# Power.net
KiCad netlist of a schematic drawn in Altium Designer
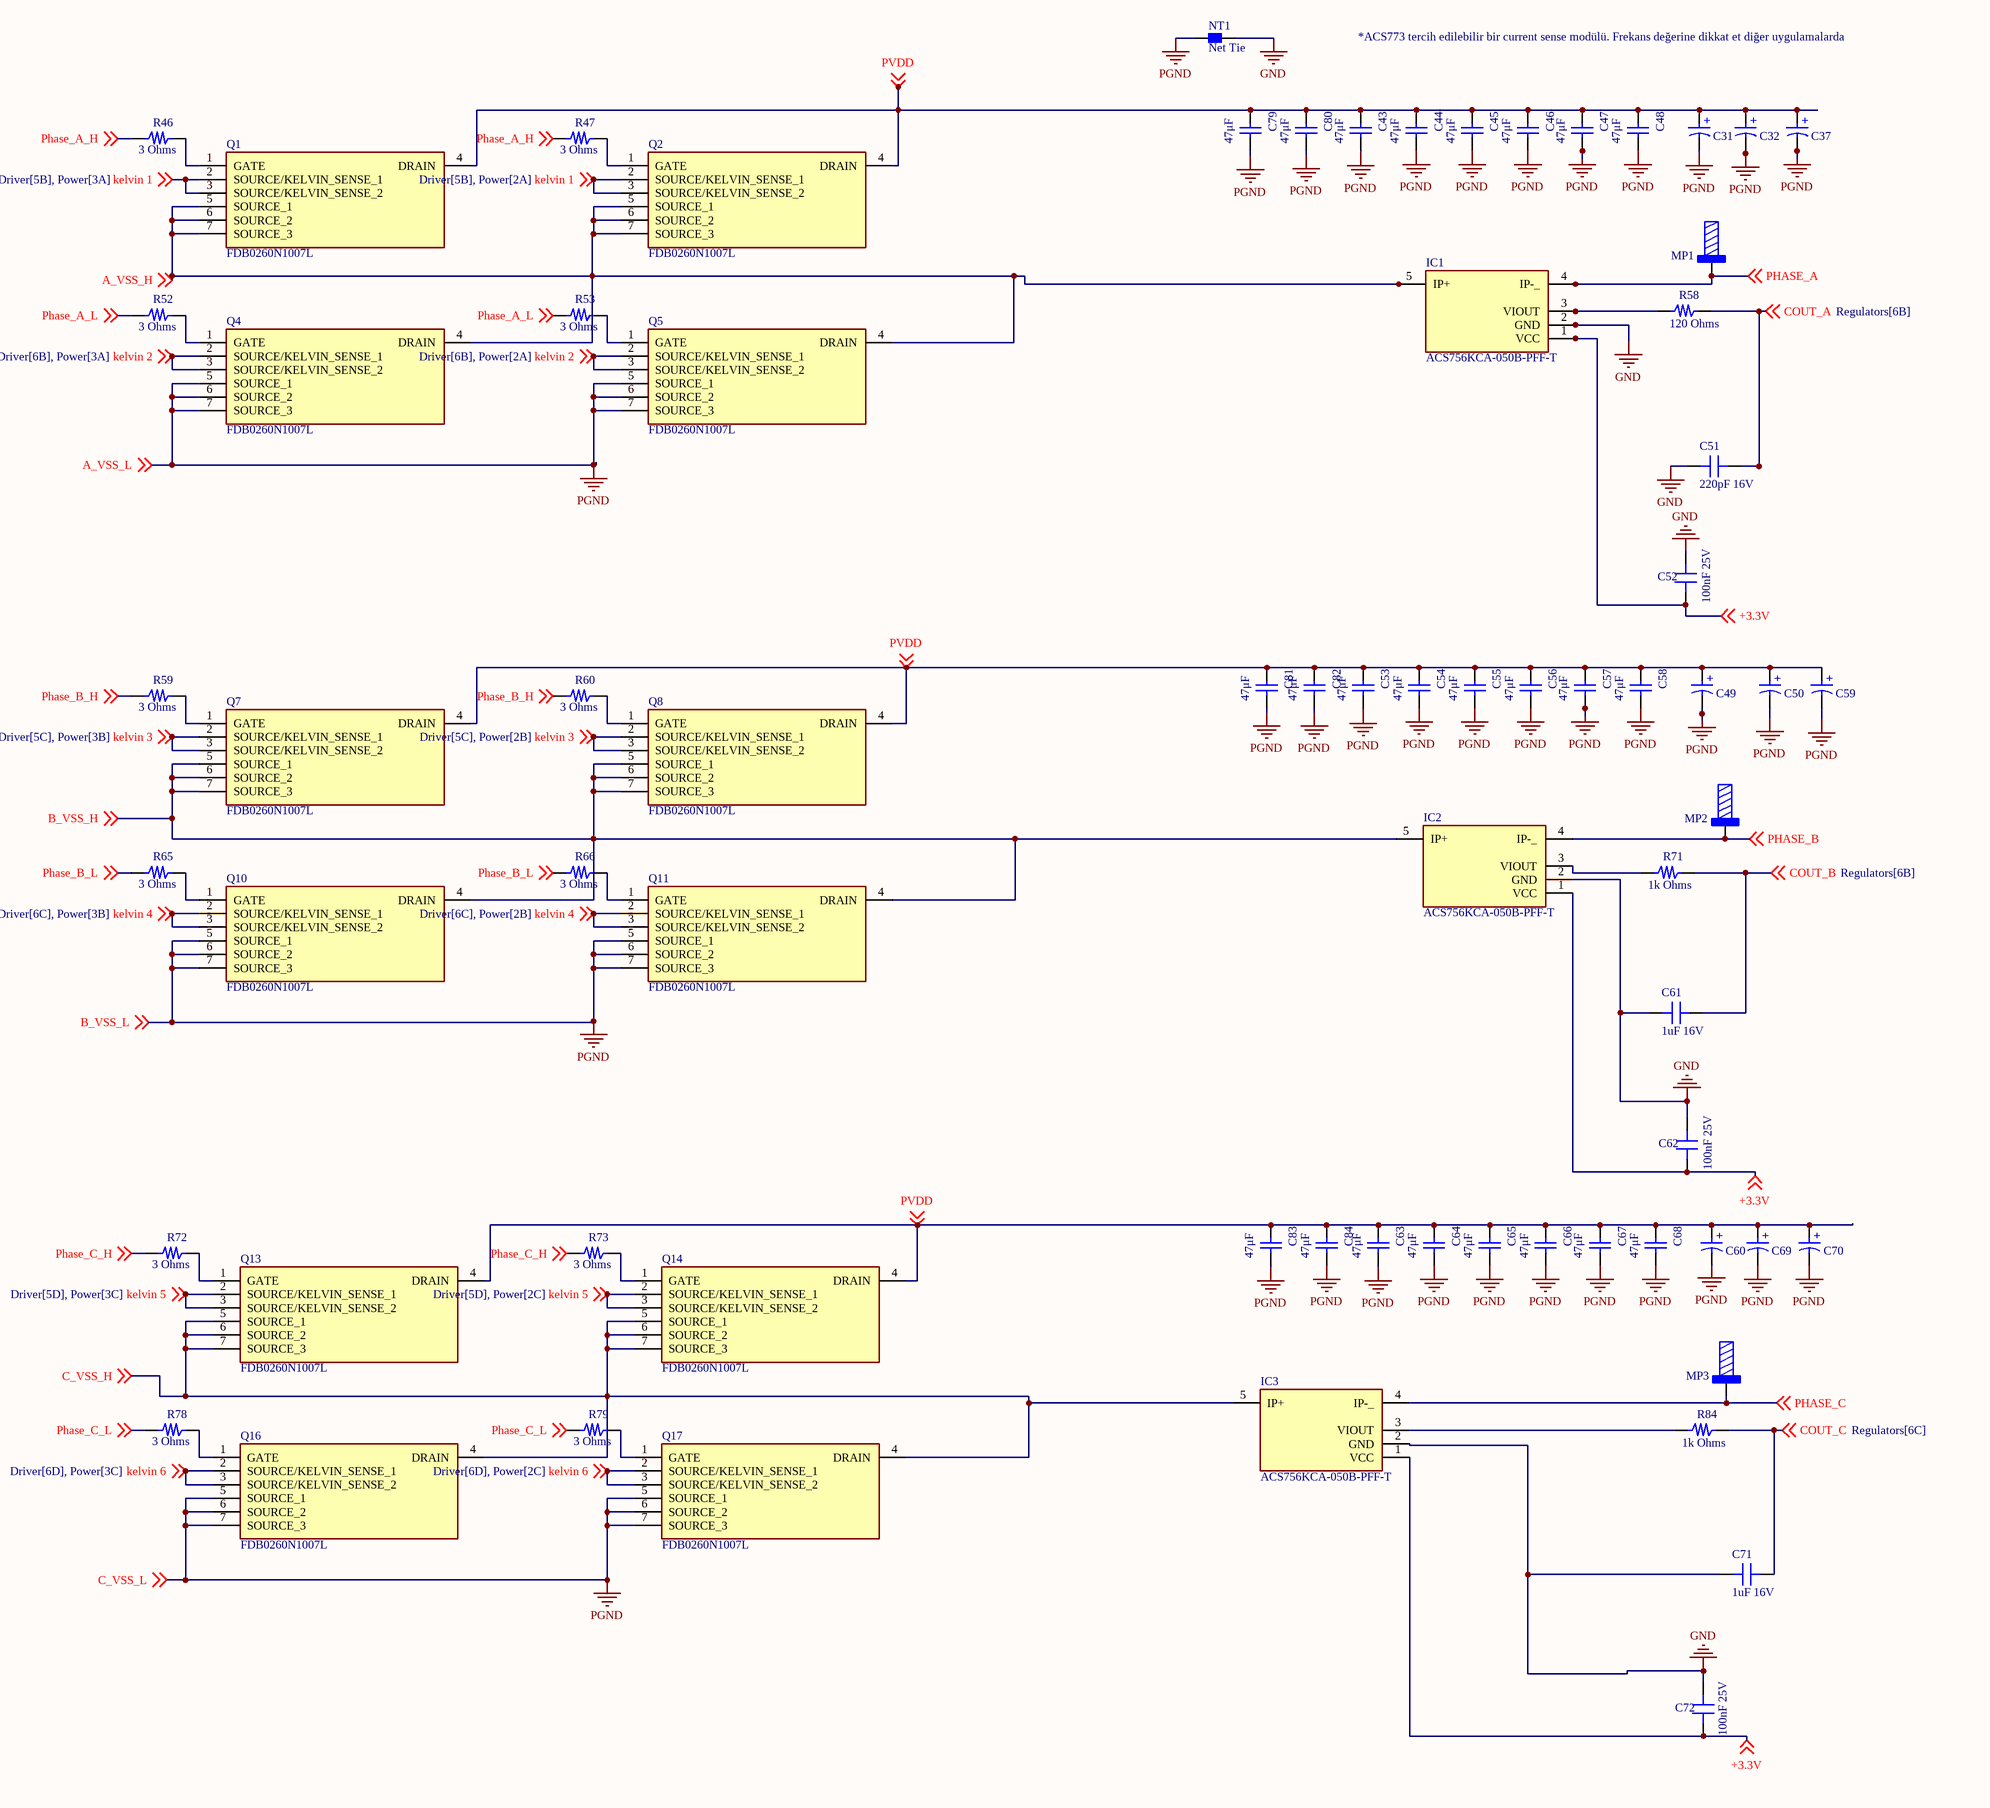
[diagram p0: Power.SchDoc]

(export (version "E")
  (design (tool "Eeschema 10.0.6"))
  (components
    (comp (ref "C31")
      (value "470µF")
      (footprint "WCAP-ATUL_D18H31.5")
      (description "WCAP-ATUL Aluminum Electrolytic Capacitor, Radial, THT, D18 x H31.5mm, 470µF, 100V")
      (fields
        (field (name "MANUFACTURER PART NUMBER") "860040881012")
        (field (name "MANUFACTURER") "Wurth Elektronik")
      )
      (libsource (lib "Altium_WCAP-ATUL (rev22e) (1)") (part "860040881012"))
    )
    (comp (ref "C32")
      (value "470µF")
      (footprint "WCAP-ATUL_D18H31.5")
      (description "WCAP-ATUL Aluminum Electrolytic Capacitor, Radial, THT, D18 x H31.5mm, 470µF, 100V")
      (fields
        (field (name "MANUFACTURER PART NUMBER") "860040881012")
        (field (name "MANUFACTURER") "Wurth Elektronik")
      )
      (libsource (lib "Altium_WCAP-ATUL (rev22e) (1)") (part "860040881012"))
    )
    (comp (ref "C37")
      (value "470µF")
      (footprint "WCAP-ATUL_D18H31.5")
      (description "WCAP-ATUL Aluminum Electrolytic Capacitor, Radial, THT, D18 x H31.5mm, 470µF, 100V")
      (fields
        (field (name "MANUFACTURER PART NUMBER") "860040881012")
        (field (name "MANUFACTURER") "Wurth Elektronik")
      )
      (libsource (lib "Altium_WCAP-ATUL (rev22e) (1)") (part "860040881012"))
    )
    (comp (ref "C43")
      (value "47μF")
      (footprint "WCAP-CSGP_1210_L3.2W2.5H2.5")
      (description "WCAP-CSGP Multilayer Ceramic Chip Capacitor, General Purpose, size 1210, X5R, 47μF, 10V")
      (fields
        (field (name "MANUFACTURER PART NUMBER") "885012109007")
        (field (name "MANUFACTURER") "Wurth Elektronik")
      )
      (libsource (lib "Altium_WCAP-CSGP (rev24c)") (part "885012109007"))
    )
    (comp (ref "C44")
      (value "47μF")
      (footprint "WCAP-CSGP_1210_L3.2W2.5H2.5")
      (description "WCAP-CSGP Multilayer Ceramic Chip Capacitor, General Purpose, size 1210, X5R, 47μF, 10V")
      (fields
        (field (name "MANUFACTURER PART NUMBER") "885012109007")
        (field (name "MANUFACTURER") "Wurth Elektronik")
      )
      (libsource (lib "Altium_WCAP-CSGP (rev24c)") (part "885012109007"))
    )
    (comp (ref "C45")
      (value "47μF")
      (footprint "WCAP-CSGP_1210_L3.2W2.5H2.5")
      (description "WCAP-CSGP Multilayer Ceramic Chip Capacitor, General Purpose, size 1210, X5R, 47μF, 10V")
      (fields
        (field (name "MANUFACTURER PART NUMBER") "885012109007")
        (field (name "MANUFACTURER") "Wurth Elektronik")
      )
      (libsource (lib "Altium_WCAP-CSGP (rev24c)") (part "885012109007"))
    )
    (comp (ref "C46")
      (value "47μF")
      (footprint "WCAP-CSGP_1210_L3.2W2.5H2.5")
      (description "WCAP-CSGP Multilayer Ceramic Chip Capacitor, General Purpose, size 1210, X5R, 47μF, 10V")
      (fields
        (field (name "MANUFACTURER PART NUMBER") "885012109007")
        (field (name "MANUFACTURER") "Wurth Elektronik")
      )
      (libsource (lib "Altium_WCAP-CSGP (rev24c)") (part "885012109007"))
    )
    (comp (ref "C47")
      (value "47μF")
      (footprint "WCAP-CSGP_1210_L3.2W2.5H2.5")
      (description "WCAP-CSGP Multilayer Ceramic Chip Capacitor, General Purpose, size 1210, X5R, 47μF, 10V")
      (fields
        (field (name "MANUFACTURER PART NUMBER") "885012109007")
        (field (name "MANUFACTURER") "Wurth Elektronik")
      )
      (libsource (lib "Altium_WCAP-CSGP (rev24c)") (part "885012109007"))
    )
    (comp (ref "C48")
      (value "47μF")
      (footprint "WCAP-CSGP_1210_L3.2W2.5H2.5")
      (description "WCAP-CSGP Multilayer Ceramic Chip Capacitor, General Purpose, size 1210, X5R, 47μF, 10V")
      (fields
        (field (name "MANUFACTURER PART NUMBER") "885012109007")
        (field (name "MANUFACTURER") "Wurth Elektronik")
      )
      (libsource (lib "Altium_WCAP-CSGP (rev24c)") (part "885012109007"))
    )
    (comp (ref "C49")
      (value "470µF")
      (footprint "WCAP-ATUL_D18H31.5")
      (description "WCAP-ATUL Aluminum Electrolytic Capacitor, Radial, THT, D18 x H31.5mm, 470µF, 100V")
      (fields
        (field (name "MANUFACTURER PART NUMBER") "860040881012")
        (field (name "MANUFACTURER") "Wurth Elektronik")
      )
      (libsource (lib "Altium_WCAP-ATUL (rev22e) (1)") (part "860040881012"))
    )
    (comp (ref "C50")
      (value "470µF")
      (footprint "WCAP-ATUL_D18H31.5")
      (description "WCAP-ATUL Aluminum Electrolytic Capacitor, Radial, THT, D18 x H31.5mm, 470µF, 100V")
      (fields
        (field (name "MANUFACTURER PART NUMBER") "860040881012")
        (field (name "MANUFACTURER") "Wurth Elektronik")
      )
      (libsource (lib "Altium_WCAP-ATUL (rev22e) (1)") (part "860040881012"))
    )
    (comp (ref "C51")
      (value "220pF 16V")
      (footprint "0603_CAP")
      (description "CL10B105KO8NNNC - MLCC (1608) 0603 1uF 16VDC ±10% X7R")
      (libsource (lib "HidroanaSCHLib") (part "CAP_0603"))
    )
    (comp (ref "C52")
      (value "100nF 25V")
      (footprint "0603_CAP")
      (description "CL10B105KO8NNNC - MLCC (1608) 0603 1uF 16VDC ±10% X7R")
      (libsource (lib "HidroanaSCHLib") (part "CAP_0603"))
    )
    (comp (ref "C53")
      (value "47μF")
      (footprint "WCAP-CSGP_1210_L3.2W2.5H2.5")
      (description "WCAP-CSGP Multilayer Ceramic Chip Capacitor, General Purpose, size 1210, X5R, 47μF, 10V")
      (fields
        (field (name "MANUFACTURER PART NUMBER") "885012109007")
        (field (name "MANUFACTURER") "Wurth Elektronik")
      )
      (libsource (lib "Altium_WCAP-CSGP (rev24c)") (part "885012109007"))
    )
    (comp (ref "C54")
      (value "47μF")
      (footprint "WCAP-CSGP_1210_L3.2W2.5H2.5")
      (description "WCAP-CSGP Multilayer Ceramic Chip Capacitor, General Purpose, size 1210, X5R, 47μF, 10V")
      (fields
        (field (name "MANUFACTURER PART NUMBER") "885012109007")
        (field (name "MANUFACTURER") "Wurth Elektronik")
      )
      (libsource (lib "Altium_WCAP-CSGP (rev24c)") (part "885012109007"))
    )
    (comp (ref "C55")
      (value "47μF")
      (footprint "WCAP-CSGP_1210_L3.2W2.5H2.5")
      (description "WCAP-CSGP Multilayer Ceramic Chip Capacitor, General Purpose, size 1210, X5R, 47μF, 10V")
      (fields
        (field (name "MANUFACTURER PART NUMBER") "885012109007")
        (field (name "MANUFACTURER") "Wurth Elektronik")
      )
      (libsource (lib "Altium_WCAP-CSGP (rev24c)") (part "885012109007"))
    )
    (comp (ref "C56")
      (value "47μF")
      (footprint "WCAP-CSGP_1210_L3.2W2.5H2.5")
      (description "WCAP-CSGP Multilayer Ceramic Chip Capacitor, General Purpose, size 1210, X5R, 47μF, 10V")
      (fields
        (field (name "MANUFACTURER PART NUMBER") "885012109007")
        (field (name "MANUFACTURER") "Wurth Elektronik")
      )
      (libsource (lib "Altium_WCAP-CSGP (rev24c)") (part "885012109007"))
    )
    (comp (ref "C57")
      (value "47μF")
      (footprint "WCAP-CSGP_1210_L3.2W2.5H2.5")
      (description "WCAP-CSGP Multilayer Ceramic Chip Capacitor, General Purpose, size 1210, X5R, 47μF, 10V")
      (fields
        (field (name "MANUFACTURER PART NUMBER") "885012109007")
        (field (name "MANUFACTURER") "Wurth Elektronik")
      )
      (libsource (lib "Altium_WCAP-CSGP (rev24c)") (part "885012109007"))
    )
    (comp (ref "C58")
      (value "47μF")
      (footprint "WCAP-CSGP_1210_L3.2W2.5H2.5")
      (description "WCAP-CSGP Multilayer Ceramic Chip Capacitor, General Purpose, size 1210, X5R, 47μF, 10V")
      (fields
        (field (name "MANUFACTURER PART NUMBER") "885012109007")
        (field (name "MANUFACTURER") "Wurth Elektronik")
      )
      (libsource (lib "Altium_WCAP-CSGP (rev24c)") (part "885012109007"))
    )
    (comp (ref "C59")
      (value "470µF")
      (footprint "WCAP-ATUL_D18H31.5")
      (description "WCAP-ATUL Aluminum Electrolytic Capacitor, Radial, THT, D18 x H31.5mm, 470µF, 100V")
      (fields
        (field (name "MANUFACTURER PART NUMBER") "860040881012")
        (field (name "MANUFACTURER") "Wurth Elektronik")
      )
      (libsource (lib "Altium_WCAP-ATUL (rev22e) (1)") (part "860040881012"))
    )
    (comp (ref "C60")
      (value "470µF")
      (footprint "WCAP-ATUL_D18H31.5")
      (description "WCAP-ATUL Aluminum Electrolytic Capacitor, Radial, THT, D18 x H31.5mm, 470µF, 100V")
      (fields
        (field (name "MANUFACTURER PART NUMBER") "860040881012")
        (field (name "MANUFACTURER") "Wurth Elektronik")
      )
      (libsource (lib "Altium_WCAP-ATUL (rev22e) (1)") (part "860040881012"))
    )
    (comp (ref "C61")
      (value "1uF 16V")
      (footprint "0603_CAP")
      (description "CL10B105KO8NNNC - MLCC (1608) 0603 1uF 16VDC ±10% X7R")
      (libsource (lib "HidroanaSCHLib") (part "CAP_0603"))
    )
    (comp (ref "C62")
      (value "100nF 25V")
      (footprint "0603_CAP")
      (description "CL10B105KO8NNNC - MLCC (1608) 0603 1uF 16VDC ±10% X7R")
      (libsource (lib "HidroanaSCHLib") (part "CAP_0603"))
    )
    (comp (ref "C63")
      (value "47μF")
      (footprint "WCAP-CSGP_1210_L3.2W2.5H2.5")
      (description "WCAP-CSGP Multilayer Ceramic Chip Capacitor, General Purpose, size 1210, X5R, 47μF, 10V")
      (fields
        (field (name "MANUFACTURER PART NUMBER") "885012109007")
        (field (name "MANUFACTURER") "Wurth Elektronik")
      )
      (libsource (lib "Altium_WCAP-CSGP (rev24c)") (part "885012109007"))
    )
    (comp (ref "C64")
      (value "47μF")
      (footprint "WCAP-CSGP_1210_L3.2W2.5H2.5")
      (description "WCAP-CSGP Multilayer Ceramic Chip Capacitor, General Purpose, size 1210, X5R, 47μF, 10V")
      (fields
        (field (name "MANUFACTURER PART NUMBER") "885012109007")
        (field (name "MANUFACTURER") "Wurth Elektronik")
      )
      (libsource (lib "Altium_WCAP-CSGP (rev24c)") (part "885012109007"))
    )
    (comp (ref "C65")
      (value "47μF")
      (footprint "WCAP-CSGP_1210_L3.2W2.5H2.5")
      (description "WCAP-CSGP Multilayer Ceramic Chip Capacitor, General Purpose, size 1210, X5R, 47μF, 10V")
      (fields
        (field (name "MANUFACTURER PART NUMBER") "885012109007")
        (field (name "MANUFACTURER") "Wurth Elektronik")
      )
      (libsource (lib "Altium_WCAP-CSGP (rev24c)") (part "885012109007"))
    )
    (comp (ref "C66")
      (value "47μF")
      (footprint "WCAP-CSGP_1210_L3.2W2.5H2.5")
      (description "WCAP-CSGP Multilayer Ceramic Chip Capacitor, General Purpose, size 1210, X5R, 47μF, 10V")
      (fields
        (field (name "MANUFACTURER PART NUMBER") "885012109007")
        (field (name "MANUFACTURER") "Wurth Elektronik")
      )
      (libsource (lib "Altium_WCAP-CSGP (rev24c)") (part "885012109007"))
    )
    (comp (ref "C67")
      (value "47μF")
      (footprint "WCAP-CSGP_1210_L3.2W2.5H2.5")
      (description "WCAP-CSGP Multilayer Ceramic Chip Capacitor, General Purpose, size 1210, X5R, 47μF, 10V")
      (fields
        (field (name "MANUFACTURER PART NUMBER") "885012109007")
        (field (name "MANUFACTURER") "Wurth Elektronik")
      )
      (libsource (lib "Altium_WCAP-CSGP (rev24c)") (part "885012109007"))
    )
    (comp (ref "C68")
      (value "47μF")
      (footprint "WCAP-CSGP_1210_L3.2W2.5H2.5")
      (description "WCAP-CSGP Multilayer Ceramic Chip Capacitor, General Purpose, size 1210, X5R, 47μF, 10V")
      (fields
        (field (name "MANUFACTURER PART NUMBER") "885012109007")
        (field (name "MANUFACTURER") "Wurth Elektronik")
      )
      (libsource (lib "Altium_WCAP-CSGP (rev24c)") (part "885012109007"))
    )
    (comp (ref "C69")
      (value "470µF")
      (footprint "WCAP-ATUL_D18H31.5")
      (description "WCAP-ATUL Aluminum Electrolytic Capacitor, Radial, THT, D18 x H31.5mm, 470µF, 100V")
      (fields
        (field (name "MANUFACTURER PART NUMBER") "860040881012")
        (field (name "MANUFACTURER") "Wurth Elektronik")
      )
      (libsource (lib "Altium_WCAP-ATUL (rev22e) (1)") (part "860040881012"))
    )
    (comp (ref "C70")
      (value "470µF")
      (footprint "WCAP-ATUL_D18H31.5")
      (description "WCAP-ATUL Aluminum Electrolytic Capacitor, Radial, THT, D18 x H31.5mm, 470µF, 100V")
      (fields
        (field (name "MANUFACTURER PART NUMBER") "860040881012")
        (field (name "MANUFACTURER") "Wurth Elektronik")
      )
      (libsource (lib "Altium_WCAP-ATUL (rev22e) (1)") (part "860040881012"))
    )
    (comp (ref "C71")
      (value "1uF 16V")
      (footprint "0603_CAP")
      (description "CL10B105KO8NNNC - MLCC (1608) 0603 1uF 16VDC ±10% X7R")
      (libsource (lib "HidroanaSCHLib") (part "CAP_0603"))
    )
    (comp (ref "C72")
      (value "100nF 25V")
      (footprint "0603_CAP")
      (description "CL10B105KO8NNNC - MLCC (1608) 0603 1uF 16VDC ±10% X7R")
      (libsource (lib "HidroanaSCHLib") (part "CAP_0603"))
    )
    (comp (ref "C79")
      (value "47μF")
      (footprint "WCAP-CSGP_1210_L3.2W2.5H2.5")
      (description "WCAP-CSGP Multilayer Ceramic Chip Capacitor, General Purpose, size 1210, X5R, 47μF, 10V")
      (fields
        (field (name "MANUFACTURER PART NUMBER") "885012109007")
        (field (name "MANUFACTURER") "Wurth Elektronik")
      )
      (libsource (lib "Altium_WCAP-CSGP (rev24c)") (part "885012109007"))
    )
    (comp (ref "C80")
      (value "47μF")
      (footprint "WCAP-CSGP_1210_L3.2W2.5H2.5")
      (description "WCAP-CSGP Multilayer Ceramic Chip Capacitor, General Purpose, size 1210, X5R, 47μF, 10V")
      (fields
        (field (name "MANUFACTURER PART NUMBER") "885012109007")
        (field (name "MANUFACTURER") "Wurth Elektronik")
      )
      (libsource (lib "Altium_WCAP-CSGP (rev24c)") (part "885012109007"))
    )
    (comp (ref "C81")
      (value "47μF")
      (footprint "WCAP-CSGP_1210_L3.2W2.5H2.5")
      (description "WCAP-CSGP Multilayer Ceramic Chip Capacitor, General Purpose, size 1210, X5R, 47μF, 10V")
      (fields
        (field (name "MANUFACTURER PART NUMBER") "885012109007")
        (field (name "MANUFACTURER") "Wurth Elektronik")
      )
      (libsource (lib "Altium_WCAP-CSGP (rev24c)") (part "885012109007"))
    )
    (comp (ref "C82")
      (value "47μF")
      (footprint "WCAP-CSGP_1210_L3.2W2.5H2.5")
      (description "WCAP-CSGP Multilayer Ceramic Chip Capacitor, General Purpose, size 1210, X5R, 47μF, 10V")
      (fields
        (field (name "MANUFACTURER PART NUMBER") "885012109007")
        (field (name "MANUFACTURER") "Wurth Elektronik")
      )
      (libsource (lib "Altium_WCAP-CSGP (rev24c)") (part "885012109007"))
    )
    (comp (ref "C83")
      (value "47μF")
      (footprint "WCAP-CSGP_1210_L3.2W2.5H2.5")
      (description "WCAP-CSGP Multilayer Ceramic Chip Capacitor, General Purpose, size 1210, X5R, 47μF, 10V")
      (fields
        (field (name "MANUFACTURER PART NUMBER") "885012109007")
        (field (name "MANUFACTURER") "Wurth Elektronik")
      )
      (libsource (lib "Altium_WCAP-CSGP (rev24c)") (part "885012109007"))
    )
    (comp (ref "C84")
      (value "47μF")
      (footprint "WCAP-CSGP_1210_L3.2W2.5H2.5")
      (description "WCAP-CSGP Multilayer Ceramic Chip Capacitor, General Purpose, size 1210, X5R, 47μF, 10V")
      (fields
        (field (name "MANUFACTURER PART NUMBER") "885012109007")
        (field (name "MANUFACTURER") "Wurth Elektronik")
      )
      (libsource (lib "Altium_WCAP-CSGP (rev24c)") (part "885012109007"))
    )
    (comp (ref "IC1")
      (value "ACS756KCA-050B-PFF-T")
      (footprint "ACS758")
      (description "Integrated Circuit")
      (libsource (lib "SamacSys (1)") (part "ACS756KCA-050B-PFF-T"))
    )
    (comp (ref "IC2")
      (value "ACS756KCA-050B-PFF-T")
      (footprint "ACS758")
      (description "Integrated Circuit")
      (libsource (lib "SamacSys (1)") (part "ACS756KCA-050B-PFF-T"))
    )
    (comp (ref "IC3")
      (value "ACS756KCA-050B-PFF-T")
      (footprint "ACS758")
      (description "Integrated Circuit")
      (libsource (lib "SamacSys (1)") (part "ACS756KCA-050B-PFF-T"))
    )
    (comp (ref "MP1")
      (value "M6 x 10mm")
      (footprint "7461098_chemical surface")
      (description "WP-SHFU REDCUBE PRESS-FIT with external thread, L13W13H15.5mm, M6 x 10mm, 250A")
      (fields
        (field (name "MANUFACTURER PART NUMBER") "7461098")
        (field (name "MANUFACTURER") "Wurth Elektronik")
      )
      (libsource (lib "Altium_WP-SHFU (rev22b)") (part "7461098"))
    )
    (comp (ref "MP2")
      (value "M6 x 10mm")
      (footprint "7461098_chemical surface")
      (description "WP-SHFU REDCUBE PRESS-FIT with external thread, L13W13H15.5mm, M6 x 10mm, 250A")
      (fields
        (field (name "MANUFACTURER PART NUMBER") "7461098")
        (field (name "MANUFACTURER") "Wurth Elektronik")
      )
      (libsource (lib "Altium_WP-SHFU (rev22b)") (part "7461098"))
    )
    (comp (ref "MP3")
      (value "M6 x 10mm")
      (footprint "7461098_chemical surface")
      (description "WP-SHFU REDCUBE PRESS-FIT with external thread, L13W13H15.5mm, M6 x 10mm, 250A")
      (fields
        (field (name "MANUFACTURER PART NUMBER") "7461098")
        (field (name "MANUFACTURER") "Wurth Elektronik")
      )
      (libsource (lib "Altium_WP-SHFU (rev22b)") (part "7461098"))
    )
    (comp (ref "NT1")
      (value "Net Tie")
      (footprint "NET TIE")
      (description "1206 size")
      (libsource (lib "HidroanaSCHLib") (part "Net Tie"))
    )
    (comp (ref "Q1")
      (value "FDB0260N1007L")
      (footprint "FDB0260N1007L")
      (description "MOSFET 100V TO263 7L JEDEC GREEN EMC")
      (fields (field (name "MOUSER PART NUMBER") "512-FDB0260N1007L"))
      (libsource (lib "FDB0260N1007L") (part "FDB0260N1007L"))
    )
    (comp (ref "Q2")
      (value "FDB0260N1007L")
      (footprint "FDB0260N1007L")
      (description "MOSFET 100V TO263 7L JEDEC GREEN EMC")
      (fields (field (name "MOUSER PART NUMBER") "512-FDB0260N1007L"))
      (libsource (lib "FDB0260N1007L") (part "FDB0260N1007L"))
    )
    (comp (ref "Q4")
      (value "FDB0260N1007L")
      (footprint "FDB0260N1007L")
      (description "MOSFET 100V TO263 7L JEDEC GREEN EMC")
      (fields (field (name "MOUSER PART NUMBER") "512-FDB0260N1007L"))
      (libsource (lib "FDB0260N1007L") (part "FDB0260N1007L"))
    )
    (comp (ref "Q5")
      (value "FDB0260N1007L")
      (footprint "FDB0260N1007L")
      (description "MOSFET 100V TO263 7L JEDEC GREEN EMC")
      (fields (field (name "MOUSER PART NUMBER") "512-FDB0260N1007L"))
      (libsource (lib "FDB0260N1007L") (part "FDB0260N1007L"))
    )
    (comp (ref "Q7")
      (value "FDB0260N1007L")
      (footprint "FDB0260N1007L")
      (description "MOSFET 100V TO263 7L JEDEC GREEN EMC")
      (fields (field (name "MOUSER PART NUMBER") "512-FDB0260N1007L"))
      (libsource (lib "FDB0260N1007L") (part "FDB0260N1007L"))
    )
    (comp (ref "Q8")
      (value "FDB0260N1007L")
      (footprint "FDB0260N1007L")
      (description "MOSFET 100V TO263 7L JEDEC GREEN EMC")
      (fields (field (name "MOUSER PART NUMBER") "512-FDB0260N1007L"))
      (libsource (lib "FDB0260N1007L") (part "FDB0260N1007L"))
    )
    (comp (ref "Q10")
      (value "FDB0260N1007L")
      (footprint "FDB0260N1007L")
      (description "MOSFET 100V TO263 7L JEDEC GREEN EMC")
      (fields (field (name "MOUSER PART NUMBER") "512-FDB0260N1007L"))
      (libsource (lib "FDB0260N1007L") (part "FDB0260N1007L"))
    )
    (comp (ref "Q11")
      (value "FDB0260N1007L")
      (footprint "FDB0260N1007L")
      (description "MOSFET 100V TO263 7L JEDEC GREEN EMC")
      (fields (field (name "MOUSER PART NUMBER") "512-FDB0260N1007L"))
      (libsource (lib "FDB0260N1007L") (part "FDB0260N1007L"))
    )
    (comp (ref "Q13")
      (value "FDB0260N1007L")
      (footprint "FDB0260N1007L")
      (description "MOSFET 100V TO263 7L JEDEC GREEN EMC")
      (fields (field (name "MOUSER PART NUMBER") "512-FDB0260N1007L"))
      (libsource (lib "FDB0260N1007L") (part "FDB0260N1007L"))
    )
    (comp (ref "Q14")
      (value "FDB0260N1007L")
      (footprint "FDB0260N1007L")
      (description "MOSFET 100V TO263 7L JEDEC GREEN EMC")
      (fields (field (name "MOUSER PART NUMBER") "512-FDB0260N1007L"))
      (libsource (lib "FDB0260N1007L") (part "FDB0260N1007L"))
    )
    (comp (ref "Q16")
      (value "FDB0260N1007L")
      (footprint "FDB0260N1007L")
      (description "MOSFET 100V TO263 7L JEDEC GREEN EMC")
      (fields (field (name "MOUSER PART NUMBER") "512-FDB0260N1007L"))
      (libsource (lib "FDB0260N1007L") (part "FDB0260N1007L"))
    )
    (comp (ref "Q17")
      (value "FDB0260N1007L")
      (footprint "FDB0260N1007L")
      (description "MOSFET 100V TO263 7L JEDEC GREEN EMC")
      (fields (field (name "MOUSER PART NUMBER") "512-FDB0260N1007L"))
      (libsource (lib "FDB0260N1007L") (part "FDB0260N1007L"))
    )
    (comp (ref "R46")
      (value "3 Ohms")
      (footprint "0805_RES")
      (description "0805")
      (fields (field (name "POWER") "1/8 W"))
      (libsource (lib "HidroanaSCHLib") (part "RES_0805"))
    )
    (comp (ref "R47")
      (value "3 Ohms")
      (footprint "0805_RES")
      (description "0805")
      (fields (field (name "POWER") "1/8 W"))
      (libsource (lib "HidroanaSCHLib") (part "RES_0805"))
    )
    (comp (ref "R52")
      (value "3 Ohms")
      (footprint "0805_RES")
      (description "0805")
      (fields (field (name "POWER") "1/8 W"))
      (libsource (lib "HidroanaSCHLib") (part "RES_0805"))
    )
    (comp (ref "R53")
      (value "3 Ohms")
      (footprint "0805_RES")
      (description "0805")
      (fields (field (name "POWER") "1/8 W"))
      (libsource (lib "HidroanaSCHLib") (part "RES_0805"))
    )
    (comp (ref "R58")
      (value "120 Ohms")
      (footprint "0603_RES")
      (libsource (lib "HidroanaSCHLib") (part "1k Ohms"))
    )
    (comp (ref "R59")
      (value "3 Ohms")
      (footprint "0805_RES")
      (description "0805")
      (fields (field (name "POWER") "1/8 W"))
      (libsource (lib "HidroanaSCHLib") (part "RES_0805"))
    )
    (comp (ref "R60")
      (value "3 Ohms")
      (footprint "0805_RES")
      (description "0805")
      (fields (field (name "POWER") "1/8 W"))
      (libsource (lib "HidroanaSCHLib") (part "RES_0805"))
    )
    (comp (ref "R65")
      (value "3 Ohms")
      (footprint "0805_RES")
      (description "0805")
      (fields (field (name "POWER") "1/8 W"))
      (libsource (lib "HidroanaSCHLib") (part "RES_0805"))
    )
    (comp (ref "R66")
      (value "3 Ohms")
      (footprint "0805_RES")
      (description "0805")
      (fields (field (name "POWER") "1/8 W"))
      (libsource (lib "HidroanaSCHLib") (part "RES_0805"))
    )
    (comp (ref "R71")
      (value "1k Ohms")
      (footprint "0603_RES")
      (libsource (lib "HidroanaSCHLib") (part "1k Ohms"))
    )
    (comp (ref "R72")
      (value "3 Ohms")
      (footprint "0805_RES")
      (description "0805")
      (fields (field (name "POWER") "1/8 W"))
      (libsource (lib "HidroanaSCHLib") (part "RES_0805"))
    )
    (comp (ref "R73")
      (value "3 Ohms")
      (footprint "0805_RES")
      (description "0805")
      (fields (field (name "POWER") "1/8 W"))
      (libsource (lib "HidroanaSCHLib") (part "RES_0805"))
    )
    (comp (ref "R78")
      (value "3 Ohms")
      (footprint "0805_RES")
      (description "0805")
      (fields (field (name "POWER") "1/8 W"))
      (libsource (lib "HidroanaSCHLib") (part "RES_0805"))
    )
    (comp (ref "R79")
      (value "3 Ohms")
      (footprint "0805_RES")
      (description "0805")
      (fields (field (name "POWER") "1/8 W"))
      (libsource (lib "HidroanaSCHLib") (part "RES_0805"))
    )
    (comp (ref "R84")
      (value "1k Ohms")
      (footprint "0603_RES")
      (libsource (lib "HidroanaSCHLib") (part "1k Ohms"))
    )
  )
  (nets
    (net (code "1") (name "+3.3V") (class "Default")
      (node (ref "C52") (pin "1") (pinfunction "1_1") (pintype "passive"))
      (node (ref "C62") (pin "1") (pinfunction "1_1") (pintype "passive"))
      (node (ref "C72") (pin "1") (pinfunction "1_1") (pintype "passive"))
      (node (ref "IC1") (pin "1") (pinfunction "VCC_1") (pintype "passive"))
      (node (ref "IC2") (pin "1") (pinfunction "VCC_1") (pintype "passive"))
      (node (ref "IC3") (pin "1") (pinfunction "VCC_1") (pintype "passive"))
    )
    (net (code "2") (name "A_VSS_H") (class "Default")
      (node (ref "IC1") (pin "5") (pinfunction "IP+_5") (pintype "passive"))
      (node (ref "Q1") (pin "5") (pinfunction "SOURCE_1_5") (pintype "passive"))
      (node (ref "Q1") (pin "6") (pinfunction "SOURCE_2_6") (pintype "passive"))
      (node (ref "Q1") (pin "7") (pinfunction "SOURCE_3_7") (pintype "passive"))
      (node (ref "Q2") (pin "5") (pinfunction "SOURCE_1_5") (pintype "passive"))
      (node (ref "Q2") (pin "6") (pinfunction "SOURCE_2_6") (pintype "passive"))
      (node (ref "Q2") (pin "7") (pinfunction "SOURCE_3_7") (pintype "passive"))
      (node (ref "Q4") (pin "4") (pinfunction "DRAIN_4") (pintype "passive"))
      (node (ref "Q5") (pin "4") (pinfunction "DRAIN_4") (pintype "passive"))
    )
    (net (code "3") (name "A_VSS_L") (class "Default")
      (node (ref "C31") (pin "2") (pinfunction "N_2") (pintype "passive"))
      (node (ref "C32") (pin "2") (pinfunction "N_2") (pintype "passive"))
      (node (ref "C37") (pin "2") (pinfunction "N_2") (pintype "passive"))
      (node (ref "C43") (pin "2") (pinfunction "2_2") (pintype "passive"))
      (node (ref "C44") (pin "2") (pinfunction "2_2") (pintype "passive"))
      (node (ref "C45") (pin "2") (pinfunction "2_2") (pintype "passive"))
      (node (ref "C46") (pin "2") (pinfunction "2_2") (pintype "passive"))
      (node (ref "C47") (pin "2") (pinfunction "2_2") (pintype "passive"))
      (node (ref "C48") (pin "2") (pinfunction "2_2") (pintype "passive"))
      (node (ref "C49") (pin "2") (pinfunction "N_2") (pintype "passive"))
      (node (ref "C50") (pin "2") (pinfunction "N_2") (pintype "passive"))
      (node (ref "C53") (pin "2") (pinfunction "2_2") (pintype "passive"))
      (node (ref "C54") (pin "2") (pinfunction "2_2") (pintype "passive"))
      (node (ref "C55") (pin "2") (pinfunction "2_2") (pintype "passive"))
      (node (ref "C56") (pin "2") (pinfunction "2_2") (pintype "passive"))
      (node (ref "C57") (pin "2") (pinfunction "2_2") (pintype "passive"))
      (node (ref "C58") (pin "2") (pinfunction "2_2") (pintype "passive"))
      (node (ref "C59") (pin "2") (pinfunction "N_2") (pintype "passive"))
      (node (ref "C60") (pin "2") (pinfunction "N_2") (pintype "passive"))
      (node (ref "C63") (pin "2") (pinfunction "2_2") (pintype "passive"))
      (node (ref "C64") (pin "2") (pinfunction "2_2") (pintype "passive"))
      (node (ref "C65") (pin "2") (pinfunction "2_2") (pintype "passive"))
      (node (ref "C66") (pin "2") (pinfunction "2_2") (pintype "passive"))
      (node (ref "C67") (pin "2") (pinfunction "2_2") (pintype "passive"))
      (node (ref "C68") (pin "2") (pinfunction "2_2") (pintype "passive"))
      (node (ref "C69") (pin "2") (pinfunction "N_2") (pintype "passive"))
      (node (ref "C70") (pin "2") (pinfunction "N_2") (pintype "passive"))
      (node (ref "C79") (pin "2") (pinfunction "2_2") (pintype "passive"))
      (node (ref "C80") (pin "2") (pinfunction "2_2") (pintype "passive"))
      (node (ref "C81") (pin "2") (pinfunction "2_2") (pintype "passive"))
      (node (ref "C82") (pin "2") (pinfunction "2_2") (pintype "passive"))
      (node (ref "C83") (pin "2") (pinfunction "2_2") (pintype "passive"))
      (node (ref "C84") (pin "2") (pinfunction "2_2") (pintype "passive"))
      (node (ref "NT1") (pin "1") (pinfunction "1_1") (pintype "passive"))
      (node (ref "Q10") (pin "5") (pinfunction "SOURCE_1_5") (pintype "passive"))
      (node (ref "Q10") (pin "6") (pinfunction "SOURCE_2_6") (pintype "passive"))
      (node (ref "Q10") (pin "7") (pinfunction "SOURCE_3_7") (pintype "passive"))
      (node (ref "Q11") (pin "5") (pinfunction "SOURCE_1_5") (pintype "passive"))
      (node (ref "Q11") (pin "6") (pinfunction "SOURCE_2_6") (pintype "passive"))
      (node (ref "Q11") (pin "7") (pinfunction "SOURCE_3_7") (pintype "passive"))
      (node (ref "Q16") (pin "5") (pinfunction "SOURCE_1_5") (pintype "passive"))
      (node (ref "Q16") (pin "6") (pinfunction "SOURCE_2_6") (pintype "passive"))
      (node (ref "Q16") (pin "7") (pinfunction "SOURCE_3_7") (pintype "passive"))
      (node (ref "Q17") (pin "5") (pinfunction "SOURCE_1_5") (pintype "passive"))
      (node (ref "Q17") (pin "6") (pinfunction "SOURCE_2_6") (pintype "passive"))
      (node (ref "Q17") (pin "7") (pinfunction "SOURCE_3_7") (pintype "passive"))
      (node (ref "Q4") (pin "5") (pinfunction "SOURCE_1_5") (pintype "passive"))
      (node (ref "Q4") (pin "6") (pinfunction "SOURCE_2_6") (pintype "passive"))
      (node (ref "Q4") (pin "7") (pinfunction "SOURCE_3_7") (pintype "passive"))
      (node (ref "Q5") (pin "5") (pinfunction "SOURCE_1_5") (pintype "passive"))
      (node (ref "Q5") (pin "6") (pinfunction "SOURCE_2_6") (pintype "passive"))
      (node (ref "Q5") (pin "7") (pinfunction "SOURCE_3_7") (pintype "passive"))
    )
    (net (code "4") (name "B_VSS_H") (class "Default")
      (node (ref "IC2") (pin "5") (pinfunction "IP+_5") (pintype "passive"))
      (node (ref "Q10") (pin "4") (pinfunction "DRAIN_4") (pintype "passive"))
      (node (ref "Q11") (pin "4") (pinfunction "DRAIN_4") (pintype "passive"))
      (node (ref "Q7") (pin "5") (pinfunction "SOURCE_1_5") (pintype "passive"))
      (node (ref "Q7") (pin "6") (pinfunction "SOURCE_2_6") (pintype "passive"))
      (node (ref "Q7") (pin "7") (pinfunction "SOURCE_3_7") (pintype "passive"))
      (node (ref "Q8") (pin "5") (pinfunction "SOURCE_1_5") (pintype "passive"))
      (node (ref "Q8") (pin "6") (pinfunction "SOURCE_2_6") (pintype "passive"))
      (node (ref "Q8") (pin "7") (pinfunction "SOURCE_3_7") (pintype "passive"))
    )
    (net (code "5") (name "COUT_A") (class "Default")
      (node (ref "C51") (pin "2") (pinfunction "2_2") (pintype "passive"))
      (node (ref "R58") (pin "2") (pintype "passive"))
    )
    (net (code "6") (name "COUT_B") (class "Default")
      (node (ref "C61") (pin "2") (pinfunction "2_2") (pintype "passive"))
      (node (ref "R71") (pin "2") (pintype "passive"))
    )
    (net (code "7") (name "COUT_C") (class "Default")
      (node (ref "C71") (pin "2") (pinfunction "2_2") (pintype "passive"))
      (node (ref "R84") (pin "2") (pintype "passive"))
    )
    (net (code "8") (name "C_VSS_H") (class "Default")
      (node (ref "IC3") (pin "5") (pinfunction "IP+_5") (pintype "passive"))
      (node (ref "Q13") (pin "5") (pinfunction "SOURCE_1_5") (pintype "passive"))
      (node (ref "Q13") (pin "6") (pinfunction "SOURCE_2_6") (pintype "passive"))
      (node (ref "Q13") (pin "7") (pinfunction "SOURCE_3_7") (pintype "passive"))
      (node (ref "Q14") (pin "5") (pinfunction "SOURCE_1_5") (pintype "passive"))
      (node (ref "Q14") (pin "6") (pinfunction "SOURCE_2_6") (pintype "passive"))
      (node (ref "Q14") (pin "7") (pinfunction "SOURCE_3_7") (pintype "passive"))
      (node (ref "Q16") (pin "4") (pinfunction "DRAIN_4") (pintype "passive"))
      (node (ref "Q17") (pin "4") (pinfunction "DRAIN_4") (pintype "passive"))
    )
    (net (code "9") (name "GND") (class "Default")
      (node (ref "C51") (pin "1") (pinfunction "1_1") (pintype "passive"))
      (node (ref "C52") (pin "2") (pinfunction "2_2") (pintype "passive"))
      (node (ref "C61") (pin "1") (pinfunction "1_1") (pintype "passive"))
      (node (ref "C62") (pin "2") (pinfunction "2_2") (pintype "passive"))
      (node (ref "C71") (pin "1") (pinfunction "1_1") (pintype "passive"))
      (node (ref "C72") (pin "2") (pinfunction "2_2") (pintype "passive"))
      (node (ref "IC1") (pin "2") (pinfunction "GND_2") (pintype "passive"))
      (node (ref "IC2") (pin "2") (pinfunction "GND_2") (pintype "passive"))
      (node (ref "IC3") (pin "2") (pinfunction "GND_2") (pintype "passive"))
      (node (ref "NT1") (pin "2") (pinfunction "2_2") (pintype "passive"))
    )
    (net (code "10") (name "Net-(IC1-VIOUT)") (class "Default")
      (node (ref "IC1") (pin "3") (pinfunction "VIOUT_3") (pintype "passive"))
      (node (ref "R58") (pin "1") (pintype "passive"))
    )
    (net (code "11") (name "Net-(IC2-VIOUT)") (class "Default")
      (node (ref "IC2") (pin "3") (pinfunction "VIOUT_3") (pintype "passive"))
      (node (ref "R71") (pin "1") (pintype "passive"))
    )
    (net (code "12") (name "Net-(IC3-VIOUT)") (class "Default")
      (node (ref "IC3") (pin "3") (pinfunction "VIOUT_3") (pintype "passive"))
      (node (ref "R84") (pin "1") (pintype "passive"))
    )
    (net (code "13") (name "Net-(Q1-GATE)") (class "Default")
      (node (ref "Q1") (pin "1") (pinfunction "GATE_1") (pintype "passive"))
      (node (ref "R46") (pin "2") (pintype "passive"))
    )
    (net (code "14") (name "Net-(Q2-GATE)") (class "Default")
      (node (ref "Q2") (pin "1") (pinfunction "GATE_1") (pintype "passive"))
      (node (ref "R47") (pin "2") (pintype "passive"))
    )
    (net (code "15") (name "Net-(Q4-GATE)") (class "Default")
      (node (ref "Q4") (pin "1") (pinfunction "GATE_1") (pintype "passive"))
      (node (ref "R52") (pin "2") (pintype "passive"))
    )
    (net (code "16") (name "Net-(Q5-GATE)") (class "Default")
      (node (ref "Q5") (pin "1") (pinfunction "GATE_1") (pintype "passive"))
      (node (ref "R53") (pin "2") (pintype "passive"))
    )
    (net (code "17") (name "Net-(Q7-GATE)") (class "Default")
      (node (ref "Q7") (pin "1") (pinfunction "GATE_1") (pintype "passive"))
      (node (ref "R59") (pin "2") (pintype "passive"))
    )
    (net (code "18") (name "Net-(Q8-GATE)") (class "Default")
      (node (ref "Q8") (pin "1") (pinfunction "GATE_1") (pintype "passive"))
      (node (ref "R60") (pin "2") (pintype "passive"))
    )
    (net (code "19") (name "Net-(Q10-GATE)") (class "Default")
      (node (ref "Q10") (pin "1") (pinfunction "GATE_1") (pintype "passive"))
      (node (ref "R65") (pin "2") (pintype "passive"))
    )
    (net (code "20") (name "Net-(Q11-GATE)") (class "Default")
      (node (ref "Q11") (pin "1") (pinfunction "GATE_1") (pintype "passive"))
      (node (ref "R66") (pin "2") (pintype "passive"))
    )
    (net (code "21") (name "Net-(Q13-GATE)") (class "Default")
      (node (ref "Q13") (pin "1") (pinfunction "GATE_1") (pintype "passive"))
      (node (ref "R72") (pin "2") (pintype "passive"))
    )
    (net (code "22") (name "Net-(Q14-GATE)") (class "Default")
      (node (ref "Q14") (pin "1") (pinfunction "GATE_1") (pintype "passive"))
      (node (ref "R73") (pin "2") (pintype "passive"))
    )
    (net (code "23") (name "Net-(Q16-GATE)") (class "Default")
      (node (ref "Q16") (pin "1") (pinfunction "GATE_1") (pintype "passive"))
      (node (ref "R78") (pin "2") (pintype "passive"))
    )
    (net (code "24") (name "Net-(Q17-GATE)") (class "Default")
      (node (ref "Q17") (pin "1") (pinfunction "GATE_1") (pintype "passive"))
      (node (ref "R79") (pin "2") (pintype "passive"))
    )
    (net (code "25") (name "PHASE_A") (class "Default")
      (node (ref "IC1") (pin "4") (pinfunction "IP-__4") (pintype "passive"))
      (node (ref "MP1") (pin "1") (pinfunction "1_1") (pintype "passive"))
    )
    (net (code "26") (name "PHASE_B") (class "Default")
      (node (ref "IC2") (pin "4") (pinfunction "IP-__4") (pintype "passive"))
      (node (ref "MP2") (pin "1") (pinfunction "1_1") (pintype "passive"))
    )
    (net (code "27") (name "PHASE_C") (class "Default")
      (node (ref "IC3") (pin "4") (pinfunction "IP-__4") (pintype "passive"))
      (node (ref "MP3") (pin "1") (pinfunction "1_1") (pintype "passive"))
    )
    (net (code "28") (name "PVDD") (class "Default")
      (node (ref "C31") (pin "1") (pinfunction "P_1") (pintype "passive"))
      (node (ref "C32") (pin "1") (pinfunction "P_1") (pintype "passive"))
      (node (ref "C37") (pin "1") (pinfunction "P_1") (pintype "passive"))
      (node (ref "C43") (pin "1") (pinfunction "1_1") (pintype "passive"))
      (node (ref "C44") (pin "1") (pinfunction "1_1") (pintype "passive"))
      (node (ref "C45") (pin "1") (pinfunction "1_1") (pintype "passive"))
      (node (ref "C46") (pin "1") (pinfunction "1_1") (pintype "passive"))
      (node (ref "C47") (pin "1") (pinfunction "1_1") (pintype "passive"))
      (node (ref "C48") (pin "1") (pinfunction "1_1") (pintype "passive"))
      (node (ref "C49") (pin "1") (pinfunction "P_1") (pintype "passive"))
      (node (ref "C50") (pin "1") (pinfunction "P_1") (pintype "passive"))
      (node (ref "C53") (pin "1") (pinfunction "1_1") (pintype "passive"))
      (node (ref "C54") (pin "1") (pinfunction "1_1") (pintype "passive"))
      (node (ref "C55") (pin "1") (pinfunction "1_1") (pintype "passive"))
      (node (ref "C56") (pin "1") (pinfunction "1_1") (pintype "passive"))
      (node (ref "C57") (pin "1") (pinfunction "1_1") (pintype "passive"))
      (node (ref "C58") (pin "1") (pinfunction "1_1") (pintype "passive"))
      (node (ref "C59") (pin "1") (pinfunction "P_1") (pintype "passive"))
      (node (ref "C60") (pin "1") (pinfunction "P_1") (pintype "passive"))
      (node (ref "C63") (pin "1") (pinfunction "1_1") (pintype "passive"))
      (node (ref "C64") (pin "1") (pinfunction "1_1") (pintype "passive"))
      (node (ref "C65") (pin "1") (pinfunction "1_1") (pintype "passive"))
      (node (ref "C66") (pin "1") (pinfunction "1_1") (pintype "passive"))
      (node (ref "C67") (pin "1") (pinfunction "1_1") (pintype "passive"))
      (node (ref "C68") (pin "1") (pinfunction "1_1") (pintype "passive"))
      (node (ref "C69") (pin "1") (pinfunction "P_1") (pintype "passive"))
      (node (ref "C70") (pin "1") (pinfunction "P_1") (pintype "passive"))
      (node (ref "C79") (pin "1") (pinfunction "1_1") (pintype "passive"))
      (node (ref "C80") (pin "1") (pinfunction "1_1") (pintype "passive"))
      (node (ref "C81") (pin "1") (pinfunction "1_1") (pintype "passive"))
      (node (ref "C82") (pin "1") (pinfunction "1_1") (pintype "passive"))
      (node (ref "C83") (pin "1") (pinfunction "1_1") (pintype "passive"))
      (node (ref "C84") (pin "1") (pinfunction "1_1") (pintype "passive"))
      (node (ref "Q1") (pin "4") (pinfunction "DRAIN_4") (pintype "passive"))
      (node (ref "Q13") (pin "4") (pinfunction "DRAIN_4") (pintype "passive"))
      (node (ref "Q14") (pin "4") (pinfunction "DRAIN_4") (pintype "passive"))
      (node (ref "Q2") (pin "4") (pinfunction "DRAIN_4") (pintype "passive"))
      (node (ref "Q7") (pin "4") (pinfunction "DRAIN_4") (pintype "passive"))
      (node (ref "Q8") (pin "4") (pinfunction "DRAIN_4") (pintype "passive"))
    )
    (net (code "29") (name "Phase_A_H") (class "Default")
      (node (ref "R46") (pin "1") (pintype "passive"))
      (node (ref "R47") (pin "1") (pintype "passive"))
    )
    (net (code "30") (name "Phase_A_L") (class "Default")
      (node (ref "R52") (pin "1") (pintype "passive"))
      (node (ref "R53") (pin "1") (pintype "passive"))
    )
    (net (code "31") (name "Phase_B_H") (class "Default")
      (node (ref "R59") (pin "1") (pintype "passive"))
      (node (ref "R60") (pin "1") (pintype "passive"))
    )
    (net (code "32") (name "Phase_B_L") (class "Default")
      (node (ref "R65") (pin "1") (pintype "passive"))
      (node (ref "R66") (pin "1") (pintype "passive"))
    )
    (net (code "33") (name "Phase_C_H") (class "Default")
      (node (ref "R72") (pin "1") (pintype "passive"))
      (node (ref "R73") (pin "1") (pintype "passive"))
    )
    (net (code "34") (name "Phase_C_L") (class "Default")
      (node (ref "R78") (pin "1") (pintype "passive"))
      (node (ref "R79") (pin "1") (pintype "passive"))
    )
    (net (code "35") (name "kelvin 1") (class "Default")
      (node (ref "Q1") (pin "2") (pinfunction "SOURCE/KELVIN_SENSE_1_2") (pintype "passive"))
      (node (ref "Q1") (pin "3") (pinfunction "SOURCE/KELVIN_SENSE_2_3") (pintype "passive"))
      (node (ref "Q2") (pin "2") (pinfunction "SOURCE/KELVIN_SENSE_1_2") (pintype "passive"))
      (node (ref "Q2") (pin "3") (pinfunction "SOURCE/KELVIN_SENSE_2_3") (pintype "passive"))
    )
    (net (code "36") (name "kelvin 2") (class "Default")
      (node (ref "Q4") (pin "2") (pinfunction "SOURCE/KELVIN_SENSE_1_2") (pintype "passive"))
      (node (ref "Q4") (pin "3") (pinfunction "SOURCE/KELVIN_SENSE_2_3") (pintype "passive"))
      (node (ref "Q5") (pin "2") (pinfunction "SOURCE/KELVIN_SENSE_1_2") (pintype "passive"))
      (node (ref "Q5") (pin "3") (pinfunction "SOURCE/KELVIN_SENSE_2_3") (pintype "passive"))
    )
    (net (code "37") (name "kelvin 3") (class "Default")
      (node (ref "Q7") (pin "2") (pinfunction "SOURCE/KELVIN_SENSE_1_2") (pintype "passive"))
      (node (ref "Q7") (pin "3") (pinfunction "SOURCE/KELVIN_SENSE_2_3") (pintype "passive"))
      (node (ref "Q8") (pin "2") (pinfunction "SOURCE/KELVIN_SENSE_1_2") (pintype "passive"))
      (node (ref "Q8") (pin "3") (pinfunction "SOURCE/KELVIN_SENSE_2_3") (pintype "passive"))
    )
    (net (code "38") (name "kelvin 4") (class "Default")
      (node (ref "Q10") (pin "2") (pinfunction "SOURCE/KELVIN_SENSE_1_2") (pintype "passive"))
      (node (ref "Q10") (pin "3") (pinfunction "SOURCE/KELVIN_SENSE_2_3") (pintype "passive"))
      (node (ref "Q11") (pin "2") (pinfunction "SOURCE/KELVIN_SENSE_1_2") (pintype "passive"))
      (node (ref "Q11") (pin "3") (pinfunction "SOURCE/KELVIN_SENSE_2_3") (pintype "passive"))
    )
    (net (code "39") (name "kelvin 5") (class "Default")
      (node (ref "Q13") (pin "2") (pinfunction "SOURCE/KELVIN_SENSE_1_2") (pintype "passive"))
      (node (ref "Q13") (pin "3") (pinfunction "SOURCE/KELVIN_SENSE_2_3") (pintype "passive"))
      (node (ref "Q14") (pin "2") (pinfunction "SOURCE/KELVIN_SENSE_1_2") (pintype "passive"))
      (node (ref "Q14") (pin "3") (pinfunction "SOURCE/KELVIN_SENSE_2_3") (pintype "passive"))
    )
    (net (code "40") (name "kelvin 6") (class "Default")
      (node (ref "Q16") (pin "2") (pinfunction "SOURCE/KELVIN_SENSE_1_2") (pintype "passive"))
      (node (ref "Q16") (pin "3") (pinfunction "SOURCE/KELVIN_SENSE_2_3") (pintype "passive"))
      (node (ref "Q17") (pin "2") (pinfunction "SOURCE/KELVIN_SENSE_1_2") (pintype "passive"))
      (node (ref "Q17") (pin "3") (pinfunction "SOURCE/KELVIN_SENSE_2_3") (pintype "passive"))
    )
  )
)
